# IRcircuit.net
KiCad netlist of a schematic drawn in EAGLE
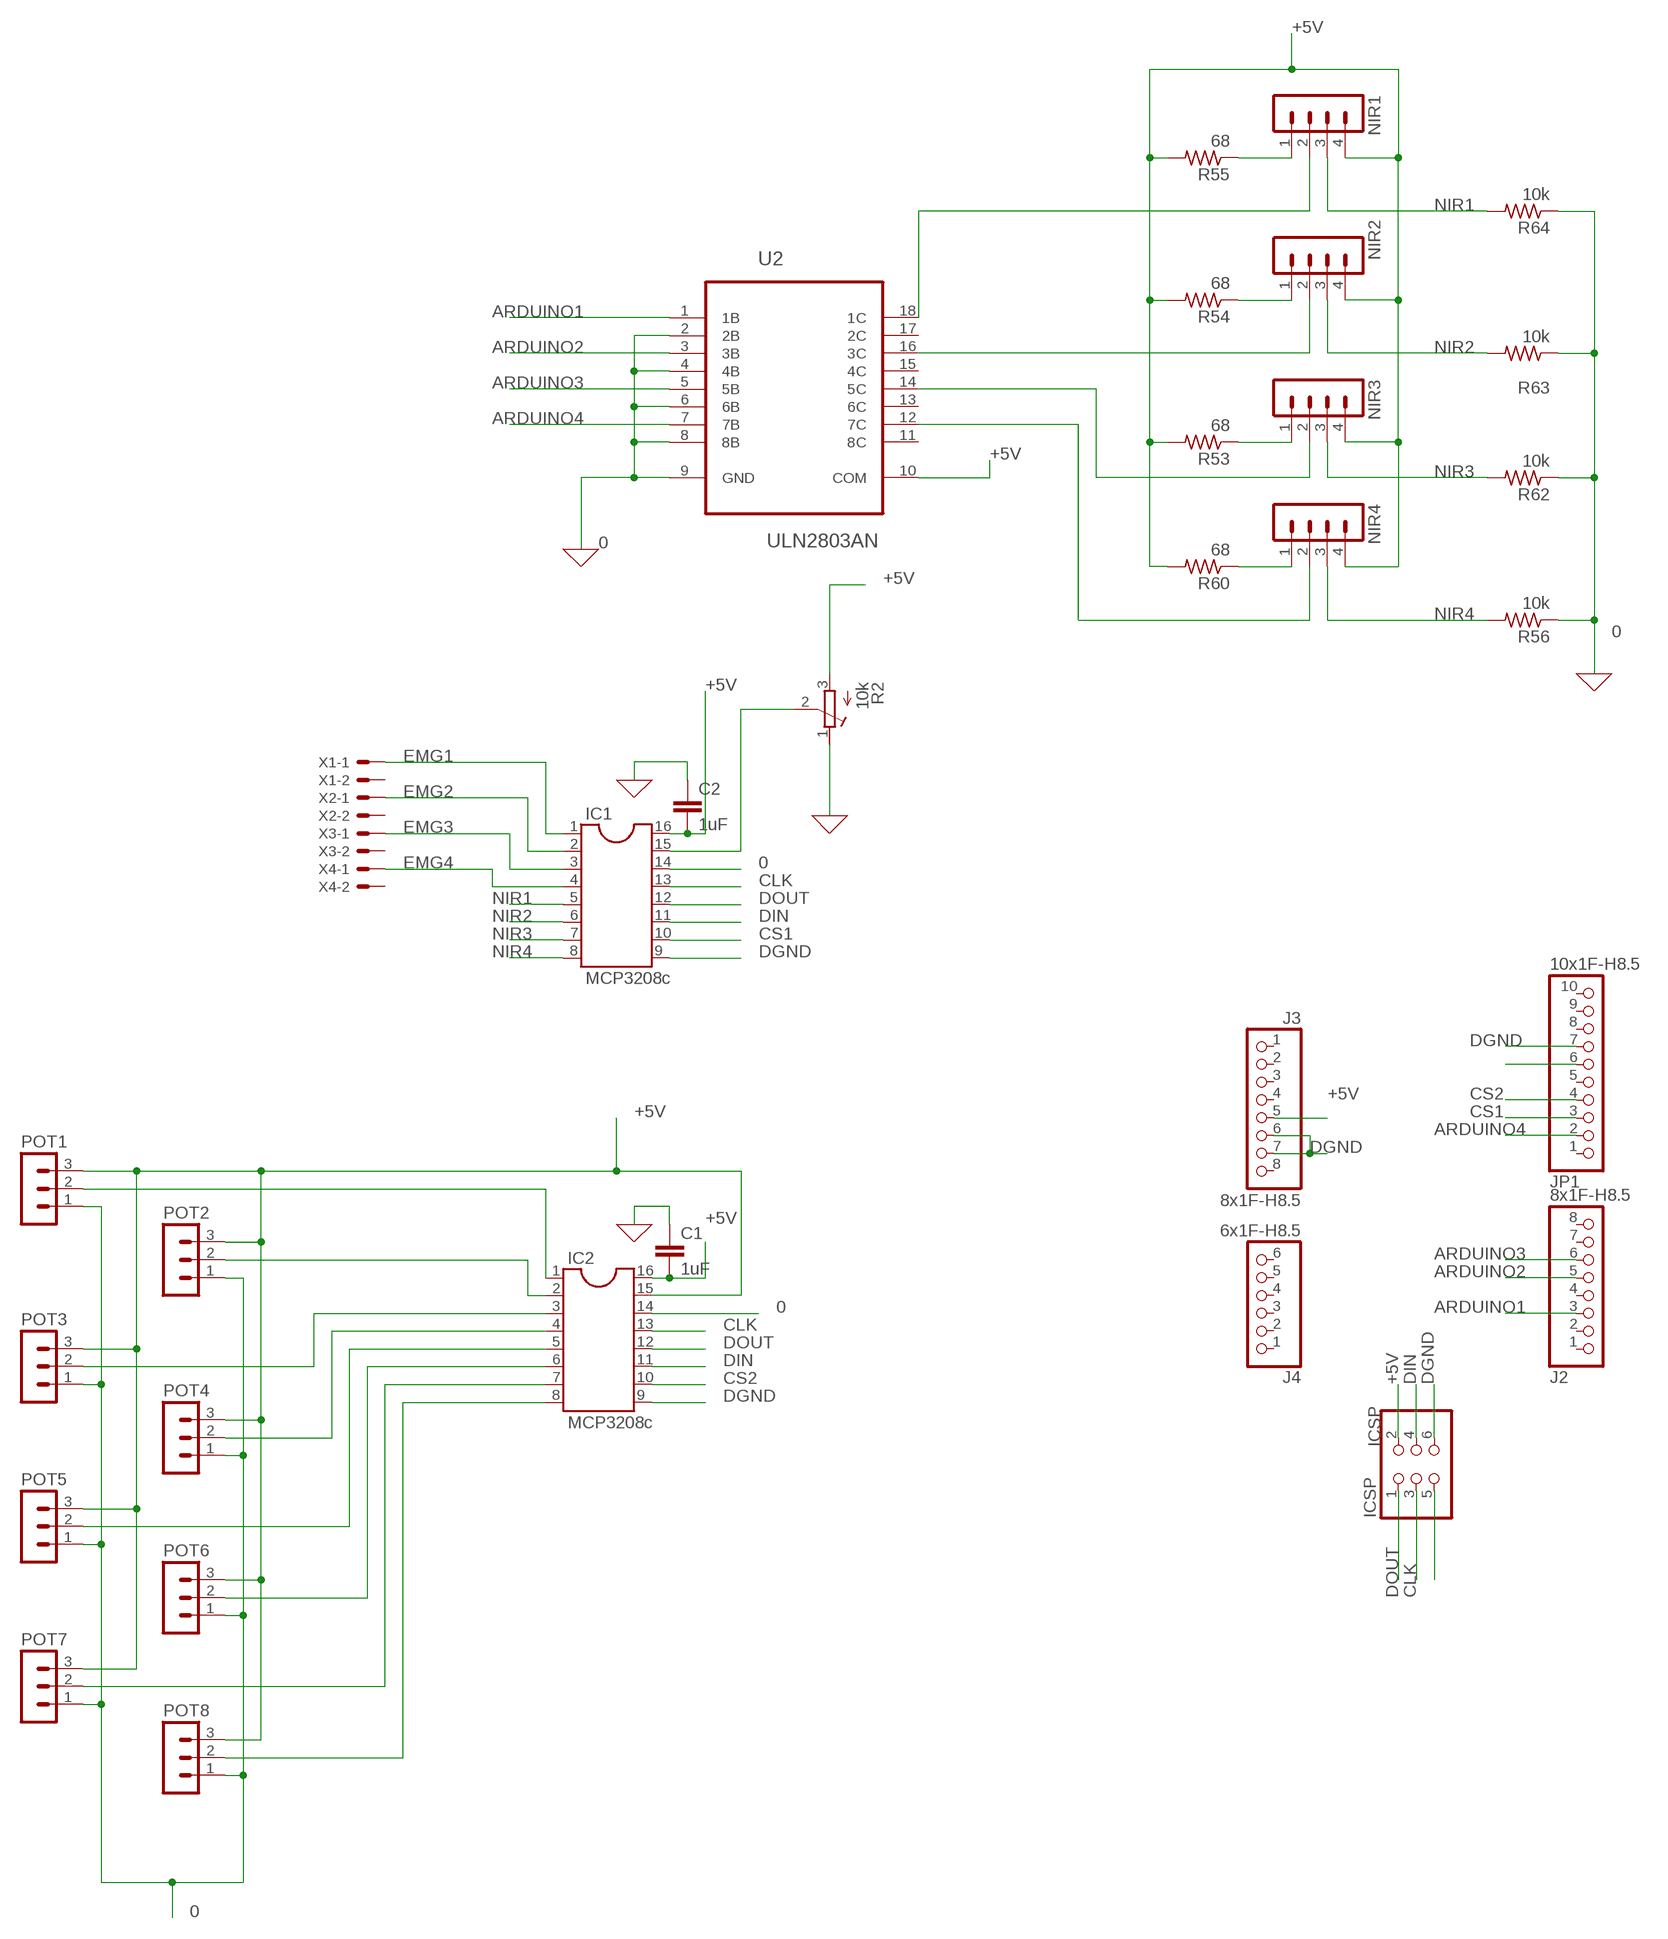
[diagram p0: schematic, sheet 1]

(export (version "E")
  (design (tool "Eeschema 10.0.6"))
  (components
    (comp (ref "C1")
      (value "1uF")
      (footprint "eagle-import:C050-025X075")
      (libsource (lib "eagle-import") (part "C-EU050-025X075"))
    )
    (comp (ref "C2")
      (value "1uF")
      (footprint "eagle-import:C050-025X075")
      (libsource (lib "eagle-import") (part "C-EU050-025X075"))
    )
    (comp (ref "IC1")
      (value "MCP3208c")
      (footprint "eagle-import:DIL16")
      (libsource (lib "eagle-import") (part "DIL16"))
    )
    (comp (ref "IC2")
      (value "MCP3208c")
      (footprint "eagle-import:DIL16")
      (libsource (lib "eagle-import") (part "DIL16"))
    )
    (comp (ref "ICSP")
      (value "ICSP")
      (footprint "eagle-import:2X03")
      (libsource (lib "eagle-import") (part "PINHD-2X3"))
    )
    (comp (ref "J2")
      (value "8x1F-H8.5")
      (footprint "eagle-import:1X08")
      (libsource (lib "eagle-import") (part "PINHD-1X8"))
    )
    (comp (ref "J3")
      (value "8x1F-H8.5")
      (footprint "eagle-import:1X08")
      (libsource (lib "eagle-import") (part "PINHD-1X8"))
    )
    (comp (ref "J4")
      (value "6x1F-H8.5")
      (footprint "eagle-import:1X06")
      (libsource (lib "eagle-import") (part "PINHD-1X6"))
    )
    (comp (ref "JP1")
      (value "10x1F-H8.5")
      (footprint "eagle-import:1X10")
      (libsource (lib "eagle-import") (part "PINHD-1X10"))
    )
    (comp (ref "NIR1")
      (value "MA04-1")
      (footprint "eagle-import:MA04-1")
      (libsource (lib "eagle-import") (part "MA04-1"))
    )
    (comp (ref "NIR2")
      (value "MA04-1")
      (footprint "eagle-import:MA04-1")
      (libsource (lib "eagle-import") (part "MA04-1"))
    )
    (comp (ref "NIR3")
      (value "MA04-1")
      (footprint "eagle-import:MA04-1")
      (libsource (lib "eagle-import") (part "MA04-1"))
    )
    (comp (ref "NIR4")
      (value "MA04-1")
      (footprint "eagle-import:MA04-1")
      (libsource (lib "eagle-import") (part "MA04-1"))
    )
    (comp (ref "POT1")
      (value "MA03-1")
      (footprint "eagle-import:MA03-1")
      (libsource (lib "eagle-import") (part "MA03-1"))
    )
    (comp (ref "POT2")
      (value "MA03-1")
      (footprint "eagle-import:MA03-1")
      (libsource (lib "eagle-import") (part "MA03-1"))
    )
    (comp (ref "POT3")
      (value "MA03-1")
      (footprint "eagle-import:MA03-1")
      (libsource (lib "eagle-import") (part "MA03-1"))
    )
    (comp (ref "POT4")
      (value "MA03-1")
      (footprint "eagle-import:MA03-1")
      (libsource (lib "eagle-import") (part "MA03-1"))
    )
    (comp (ref "POT5")
      (value "MA03-1")
      (footprint "eagle-import:MA03-1")
      (libsource (lib "eagle-import") (part "MA03-1"))
    )
    (comp (ref "POT6")
      (value "MA03-1")
      (footprint "eagle-import:MA03-1")
      (libsource (lib "eagle-import") (part "MA03-1"))
    )
    (comp (ref "POT7")
      (value "MA03-1")
      (footprint "eagle-import:MA03-1")
      (libsource (lib "eagle-import") (part "MA03-1"))
    )
    (comp (ref "POT8")
      (value "MA03-1")
      (footprint "eagle-import:MA03-1")
      (libsource (lib "eagle-import") (part "MA03-1"))
    )
    (comp (ref "R2")
      (value "10k")
      (footprint "eagle-import:RTRIMT93YA")
      (libsource (lib "eagle-import") (part "R-TRIMMT93YA"))
    )
    (comp (ref "R53")
      (value "68")
      (footprint "eagle-import:0207_12")
      (libsource (lib "eagle-import") (part "R-US_0207/12"))
    )
    (comp (ref "R54")
      (value "68")
      (footprint "eagle-import:0207_12")
      (libsource (lib "eagle-import") (part "R-US_0207/12"))
    )
    (comp (ref "R55")
      (value "68")
      (footprint "eagle-import:0207_12")
      (libsource (lib "eagle-import") (part "R-US_0207/12"))
    )
    (comp (ref "R56")
      (value "10k")
      (footprint "eagle-import:0207_12")
      (libsource (lib "eagle-import") (part "R-US_0207/12"))
    )
    (comp (ref "R60")
      (value "68")
      (footprint "eagle-import:0207_12")
      (libsource (lib "eagle-import") (part "R-US_0207/12"))
    )
    (comp (ref "R62")
      (value "10k")
      (footprint "eagle-import:0207_12")
      (libsource (lib "eagle-import") (part "R-US_0207/12"))
    )
    (comp (ref "R63")
      (value "10k")
      (footprint "eagle-import:0207_12")
      (libsource (lib "eagle-import") (part "R-US_0207/12"))
    )
    (comp (ref "R64")
      (value "10k")
      (footprint "eagle-import:0207_12")
      (libsource (lib "eagle-import") (part "R-US_0207/12"))
    )
    (comp (ref "U2")
      (value "ULN2803AN")
      (footprint "eagle-import:DIP254P762X393-18")
      (libsource (lib "eagle-import") (part "ULN2803AN"))
    )
    (comp (ref "X1")
      (value "332-02")
      (footprint "eagle-import:332-02")
      (libsource (lib "eagle-import") (part "332-02"))
    )
    (comp (ref "X2")
      (value "332-02")
      (footprint "eagle-import:332-02")
      (libsource (lib "eagle-import") (part "332-02"))
    )
    (comp (ref "X3")
      (value "332-02")
      (footprint "eagle-import:332-02")
      (libsource (lib "eagle-import") (part "332-02"))
    )
    (comp (ref "X4")
      (value "332-02")
      (footprint "eagle-import:332-02")
      (libsource (lib "eagle-import") (part "332-02"))
    )
  )
  (nets
    (net (code "1") (name "+5V") (class "Default")
      (node (ref "C1") (pin "2") (pinfunction "2_2") (pintype "passive"))
      (node (ref "C2") (pin "2") (pinfunction "2_2") (pintype "passive"))
      (node (ref "IC1") (pin "16") (pinfunction "16_16") (pintype "passive"))
      (node (ref "IC2") (pin "15") (pinfunction "15_15") (pintype "passive"))
      (node (ref "IC2") (pin "16") (pinfunction "16_16") (pintype "passive"))
      (node (ref "ICSP") (pin "2") (pinfunction "2_2") (pintype "passive"))
      (node (ref "J3") (pin "5") (pinfunction "5_5") (pintype "passive"))
      (node (ref "NIR1") (pin "4") (pinfunction "4_4") (pintype "passive"))
      (node (ref "NIR2") (pin "4") (pinfunction "4_4") (pintype "passive"))
      (node (ref "NIR3") (pin "4") (pinfunction "4_4") (pintype "passive"))
      (node (ref "NIR4") (pin "4") (pinfunction "4_4") (pintype "passive"))
      (node (ref "POT1") (pin "3") (pinfunction "3_3") (pintype "passive"))
      (node (ref "POT2") (pin "3") (pinfunction "3_3") (pintype "passive"))
      (node (ref "POT3") (pin "3") (pinfunction "3_3") (pintype "passive"))
      (node (ref "POT4") (pin "3") (pinfunction "3_3") (pintype "passive"))
      (node (ref "POT5") (pin "3") (pinfunction "3_3") (pintype "passive"))
      (node (ref "POT6") (pin "3") (pinfunction "3_3") (pintype "passive"))
      (node (ref "POT7") (pin "3") (pinfunction "3_3") (pintype "passive"))
      (node (ref "POT8") (pin "3") (pinfunction "3_3") (pintype "passive"))
      (node (ref "R2") (pin "3") (pinfunction "A_3") (pintype "passive"))
      (node (ref "R53") (pin "2") (pinfunction "2_2") (pintype "passive"))
      (node (ref "R54") (pin "2") (pinfunction "2_2") (pintype "passive"))
      (node (ref "R55") (pin "2") (pinfunction "2_2") (pintype "passive"))
      (node (ref "R60") (pin "2") (pinfunction "2_2") (pintype "passive"))
      (node (ref "U2") (pin "10") (pinfunction "COM_10") (pintype "output"))
    )
    (net (code "2") (name "0") (class "Default")
      (node (ref "C1") (pin "1") (pinfunction "1_1") (pintype "passive"))
      (node (ref "C2") (pin "1") (pinfunction "1_1") (pintype "passive"))
      (node (ref "IC1") (pin "14") (pinfunction "14_14") (pintype "passive"))
      (node (ref "IC2") (pin "14") (pinfunction "14_14") (pintype "passive"))
      (node (ref "POT1") (pin "1") (pinfunction "1_1") (pintype "passive"))
      (node (ref "POT2") (pin "1") (pinfunction "1_1") (pintype "passive"))
      (node (ref "POT3") (pin "1") (pinfunction "1_1") (pintype "passive"))
      (node (ref "POT4") (pin "1") (pinfunction "1_1") (pintype "passive"))
      (node (ref "POT5") (pin "1") (pinfunction "1_1") (pintype "passive"))
      (node (ref "POT6") (pin "1") (pinfunction "1_1") (pintype "passive"))
      (node (ref "POT7") (pin "1") (pinfunction "1_1") (pintype "passive"))
      (node (ref "POT8") (pin "1") (pinfunction "1_1") (pintype "passive"))
      (node (ref "R2") (pin "1") (pinfunction "E_1") (pintype "passive"))
      (node (ref "R56") (pin "1") (pinfunction "1_1") (pintype "passive"))
      (node (ref "R62") (pin "1") (pinfunction "1_1") (pintype "passive"))
      (node (ref "R63") (pin "1") (pinfunction "1_1") (pintype "passive"))
      (node (ref "R64") (pin "1") (pinfunction "1_1") (pintype "passive"))
      (node (ref "U2") (pin "2") (pinfunction "2B_2") (pintype "input"))
      (node (ref "U2") (pin "4") (pinfunction "4B_4") (pintype "input"))
      (node (ref "U2") (pin "6") (pinfunction "6B_6") (pintype "input"))
      (node (ref "U2") (pin "8") (pinfunction "8B_8") (pintype "input"))
      (node (ref "U2") (pin "9") (pinfunction "GND_9") (pintype "passive"))
    )
    (net (code "3") (name "ARDUINO1") (class "Default")
      (node (ref "J2") (pin "3") (pinfunction "3_3") (pintype "passive"))
      (node (ref "U2") (pin "1") (pinfunction "1B_1") (pintype "input"))
    )
    (net (code "4") (name "ARDUINO2") (class "Default")
      (node (ref "J2") (pin "5") (pinfunction "5_5") (pintype "passive"))
      (node (ref "U2") (pin "3") (pinfunction "3B_3") (pintype "input"))
    )
    (net (code "5") (name "ARDUINO3") (class "Default")
      (node (ref "J2") (pin "6") (pinfunction "6_6") (pintype "passive"))
      (node (ref "U2") (pin "5") (pinfunction "5B_5") (pintype "input"))
    )
    (net (code "6") (name "ARDUINO4") (class "Default")
      (node (ref "JP1") (pin "2") (pinfunction "2_2") (pintype "passive"))
      (node (ref "U2") (pin "7") (pinfunction "7B_7") (pintype "input"))
    )
    (net (code "7") (name "CLK") (class "Default")
      (node (ref "IC1") (pin "13") (pinfunction "13_13") (pintype "passive"))
      (node (ref "IC2") (pin "13") (pinfunction "13_13") (pintype "passive"))
      (node (ref "ICSP") (pin "3") (pinfunction "3_3") (pintype "passive"))
    )
    (net (code "8") (name "CS1") (class "Default")
      (node (ref "IC1") (pin "10") (pinfunction "10_10") (pintype "passive"))
      (node (ref "JP1") (pin "3") (pinfunction "3_3") (pintype "passive"))
    )
    (net (code "9") (name "CS2") (class "Default")
      (node (ref "IC2") (pin "10") (pinfunction "10_10") (pintype "passive"))
      (node (ref "JP1") (pin "4") (pinfunction "4_4") (pintype "passive"))
    )
    (net (code "10") (name "DGND") (class "Default")
      (node (ref "IC1") (pin "9") (pinfunction "9_9") (pintype "passive"))
      (node (ref "IC2") (pin "9") (pinfunction "9_9") (pintype "passive"))
      (node (ref "ICSP") (pin "6") (pinfunction "6_6") (pintype "passive"))
      (node (ref "J3") (pin "6") (pinfunction "6_6") (pintype "passive"))
      (node (ref "J3") (pin "7") (pinfunction "7_7") (pintype "passive"))
      (node (ref "JP1") (pin "7") (pinfunction "7_7") (pintype "passive"))
    )
    (net (code "11") (name "DIN") (class "Default")
      (node (ref "IC1") (pin "11") (pinfunction "11_11") (pintype "passive"))
      (node (ref "IC2") (pin "11") (pinfunction "11_11") (pintype "passive"))
      (node (ref "ICSP") (pin "4") (pinfunction "4_4") (pintype "passive"))
    )
    (net (code "12") (name "DOUT") (class "Default")
      (node (ref "IC1") (pin "12") (pinfunction "12_12") (pintype "passive"))
      (node (ref "IC2") (pin "12") (pinfunction "12_12") (pintype "passive"))
      (node (ref "ICSP") (pin "1") (pinfunction "1_1") (pintype "passive"))
    )
    (net (code "13") (name "EMG1") (class "Default")
      (node (ref "IC1") (pin "1") (pinfunction "1_1") (pintype "passive"))
      (node (ref "X1") (pin "1") (pinfunction "S_1") (pintype "passive"))
    )
    (net (code "14") (name "EMG2") (class "Default")
      (node (ref "IC1") (pin "2") (pinfunction "2_2") (pintype "passive"))
      (node (ref "X2") (pin "1") (pinfunction "S_1") (pintype "passive"))
    )
    (net (code "15") (name "EMG3") (class "Default")
      (node (ref "IC1") (pin "3") (pinfunction "3_3") (pintype "passive"))
      (node (ref "X3") (pin "1") (pinfunction "S_1") (pintype "passive"))
    )
    (net (code "16") (name "EMG4") (class "Default")
      (node (ref "IC1") (pin "4") (pinfunction "4_4") (pintype "passive"))
      (node (ref "X4") (pin "1") (pinfunction "S_1") (pintype "passive"))
    )
    (net (code "17") (name "NIR1") (class "Default")
      (node (ref "IC1") (pin "5") (pinfunction "5_5") (pintype "passive"))
      (node (ref "NIR1") (pin "3") (pinfunction "3_3") (pintype "passive"))
      (node (ref "R64") (pin "2") (pinfunction "2_2") (pintype "passive"))
    )
    (net (code "18") (name "NIR2") (class "Default")
      (node (ref "IC1") (pin "6") (pinfunction "6_6") (pintype "passive"))
      (node (ref "NIR2") (pin "3") (pinfunction "3_3") (pintype "passive"))
      (node (ref "R63") (pin "2") (pinfunction "2_2") (pintype "passive"))
    )
    (net (code "19") (name "NIR3") (class "Default")
      (node (ref "IC1") (pin "7") (pinfunction "7_7") (pintype "passive"))
      (node (ref "NIR3") (pin "3") (pinfunction "3_3") (pintype "passive"))
      (node (ref "R62") (pin "2") (pinfunction "2_2") (pintype "passive"))
    )
    (net (code "20") (name "NIR4") (class "Default")
      (node (ref "IC1") (pin "8") (pinfunction "8_8") (pintype "passive"))
      (node (ref "NIR4") (pin "3") (pinfunction "3_3") (pintype "passive"))
      (node (ref "R56") (pin "2") (pinfunction "2_2") (pintype "passive"))
    )
    (net (code "21") (name "Net-(IC2-Pad1)") (class "Default")
      (node (ref "IC2") (pin "1") (pinfunction "1_1") (pintype "passive"))
      (node (ref "POT1") (pin "2") (pinfunction "2_2") (pintype "passive"))
    )
    (net (code "22") (name "Net-(IC2-Pad2)") (class "Default")
      (node (ref "IC2") (pin "2") (pinfunction "2_2") (pintype "passive"))
      (node (ref "POT2") (pin "2") (pinfunction "2_2") (pintype "passive"))
    )
    (net (code "23") (name "Net-(IC2-Pad3)") (class "Default")
      (node (ref "IC2") (pin "3") (pinfunction "3_3") (pintype "passive"))
      (node (ref "POT3") (pin "2") (pinfunction "2_2") (pintype "passive"))
    )
    (net (code "24") (name "Net-(IC2-Pad4)") (class "Default")
      (node (ref "IC2") (pin "4") (pinfunction "4_4") (pintype "passive"))
      (node (ref "POT4") (pin "2") (pinfunction "2_2") (pintype "passive"))
    )
    (net (code "25") (name "Net-(IC2-Pad5)") (class "Default")
      (node (ref "IC2") (pin "5") (pinfunction "5_5") (pintype "passive"))
      (node (ref "POT5") (pin "2") (pinfunction "2_2") (pintype "passive"))
    )
    (net (code "26") (name "Net-(IC2-Pad6)") (class "Default")
      (node (ref "IC2") (pin "6") (pinfunction "6_6") (pintype "passive"))
      (node (ref "POT6") (pin "2") (pinfunction "2_2") (pintype "passive"))
    )
    (net (code "27") (name "Net-(IC2-Pad7)") (class "Default")
      (node (ref "IC2") (pin "7") (pinfunction "7_7") (pintype "passive"))
      (node (ref "POT7") (pin "2") (pinfunction "2_2") (pintype "passive"))
    )
    (net (code "28") (name "Net-(IC2-Pad8)") (class "Default")
      (node (ref "IC2") (pin "8") (pinfunction "8_8") (pintype "passive"))
      (node (ref "POT8") (pin "2") (pinfunction "2_2") (pintype "passive"))
    )
    (net (code "29") (name "Net-(NIR1-Pad1)") (class "Default")
      (node (ref "NIR1") (pin "1") (pinfunction "1_1") (pintype "passive"))
      (node (ref "R55") (pin "1") (pinfunction "1_1") (pintype "passive"))
    )
    (net (code "30") (name "Net-(NIR2-Pad1)") (class "Default")
      (node (ref "NIR2") (pin "1") (pinfunction "1_1") (pintype "passive"))
      (node (ref "R54") (pin "1") (pinfunction "1_1") (pintype "passive"))
    )
    (net (code "31") (name "Net-(NIR3-Pad1)") (class "Default")
      (node (ref "NIR3") (pin "1") (pinfunction "1_1") (pintype "passive"))
      (node (ref "R53") (pin "1") (pinfunction "1_1") (pintype "passive"))
    )
    (net (code "32") (name "Net-(NIR4-Pad1)") (class "Default")
      (node (ref "NIR4") (pin "1") (pinfunction "1_1") (pintype "passive"))
      (node (ref "R60") (pin "1") (pinfunction "1_1") (pintype "passive"))
    )
    (net (code "33") (name "Net-(R2-S)") (class "Default")
      (node (ref "IC1") (pin "15") (pinfunction "15_15") (pintype "passive"))
      (node (ref "R2") (pin "2") (pinfunction "S_2") (pintype "passive"))
    )
    (net (code "34") (name "Net-(U2-1C)") (class "Default")
      (node (ref "NIR1") (pin "2") (pinfunction "2_2") (pintype "passive"))
      (node (ref "U2") (pin "18") (pinfunction "1C_18") (pintype "output"))
    )
    (net (code "35") (name "Net-(U2-3C)") (class "Default")
      (node (ref "NIR2") (pin "2") (pinfunction "2_2") (pintype "passive"))
      (node (ref "U2") (pin "16") (pinfunction "3C_16") (pintype "output"))
    )
    (net (code "36") (name "Net-(U2-5C)") (class "Default")
      (node (ref "NIR3") (pin "2") (pinfunction "2_2") (pintype "passive"))
      (node (ref "U2") (pin "14") (pinfunction "5C_14") (pintype "output"))
    )
    (net (code "37") (name "Net-(U2-7C)") (class "Default")
      (node (ref "NIR4") (pin "2") (pinfunction "2_2") (pintype "passive"))
      (node (ref "U2") (pin "12") (pinfunction "7C_12") (pintype "output"))
    )
    (net (code "38") (name "unconnected-(ICSP-Pad5)") (class "Default")
      (node (ref "ICSP") (pin "5") (pinfunction "5_5") (pintype "passive"))
    )
    (net (code "39") (name "unconnected-(J2-Pad1)") (class "Default")
      (node (ref "J2") (pin "1") (pinfunction "1_1") (pintype "passive"))
    )
    (net (code "40") (name "unconnected-(J2-Pad2)") (class "Default")
      (node (ref "J2") (pin "2") (pinfunction "2_2") (pintype "passive"))
    )
    (net (code "41") (name "unconnected-(J2-Pad4)") (class "Default")
      (node (ref "J2") (pin "4") (pinfunction "4_4") (pintype "passive"))
    )
    (net (code "42") (name "unconnected-(J2-Pad7)") (class "Default")
      (node (ref "J2") (pin "7") (pinfunction "7_7") (pintype "passive"))
    )
    (net (code "43") (name "unconnected-(J2-Pad8)") (class "Default")
      (node (ref "J2") (pin "8") (pinfunction "8_8") (pintype "passive"))
    )
    (net (code "44") (name "unconnected-(J3-Pad1)") (class "Default")
      (node (ref "J3") (pin "1") (pinfunction "1_1") (pintype "passive"))
    )
    (net (code "45") (name "unconnected-(J3-Pad2)") (class "Default")
      (node (ref "J3") (pin "2") (pinfunction "2_2") (pintype "passive"))
    )
    (net (code "46") (name "unconnected-(J3-Pad3)") (class "Default")
      (node (ref "J3") (pin "3") (pinfunction "3_3") (pintype "passive"))
    )
    (net (code "47") (name "unconnected-(J3-Pad4)") (class "Default")
      (node (ref "J3") (pin "4") (pinfunction "4_4") (pintype "passive"))
    )
    (net (code "48") (name "unconnected-(J3-Pad8)") (class "Default")
      (node (ref "J3") (pin "8") (pinfunction "8_8") (pintype "passive"))
    )
    (net (code "49") (name "unconnected-(J4-Pad1)") (class "Default")
      (node (ref "J4") (pin "1") (pinfunction "1_1") (pintype "passive"))
    )
    (net (code "50") (name "unconnected-(J4-Pad2)") (class "Default")
      (node (ref "J4") (pin "2") (pinfunction "2_2") (pintype "passive"))
    )
    (net (code "51") (name "unconnected-(J4-Pad3)") (class "Default")
      (node (ref "J4") (pin "3") (pinfunction "3_3") (pintype "passive"))
    )
    (net (code "52") (name "unconnected-(J4-Pad4)") (class "Default")
      (node (ref "J4") (pin "4") (pinfunction "4_4") (pintype "passive"))
    )
    (net (code "53") (name "unconnected-(J4-Pad5)") (class "Default")
      (node (ref "J4") (pin "5") (pinfunction "5_5") (pintype "passive"))
    )
    (net (code "54") (name "unconnected-(J4-Pad6)") (class "Default")
      (node (ref "J4") (pin "6") (pinfunction "6_6") (pintype "passive"))
    )
    (net (code "55") (name "unconnected-(JP1-Pad1)") (class "Default")
      (node (ref "JP1") (pin "1") (pinfunction "1_1") (pintype "passive"))
    )
    (net (code "56") (name "unconnected-(JP1-Pad5)") (class "Default")
      (node (ref "JP1") (pin "5") (pinfunction "5_5") (pintype "passive"))
    )
    (net (code "57") (name "unconnected-(JP1-Pad6)") (class "Default")
      (node (ref "JP1") (pin "6") (pinfunction "6_6") (pintype "passive"))
    )
    (net (code "58") (name "unconnected-(JP1-Pad8)") (class "Default")
      (node (ref "JP1") (pin "8") (pinfunction "8_8") (pintype "passive"))
    )
    (net (code "59") (name "unconnected-(JP1-Pad9)") (class "Default")
      (node (ref "JP1") (pin "9") (pinfunction "9_9") (pintype "passive"))
    )
    (net (code "60") (name "unconnected-(JP1-Pad10)") (class "Default")
      (node (ref "JP1") (pin "10") (pinfunction "10_10") (pintype "passive"))
    )
    (net (code "61") (name "unconnected-(U2-2C-Pad17)") (class "Default")
      (node (ref "U2") (pin "17") (pinfunction "2C_17") (pintype "output"))
    )
    (net (code "62") (name "unconnected-(U2-4C-Pad15)") (class "Default")
      (node (ref "U2") (pin "15") (pinfunction "4C_15") (pintype "output"))
    )
    (net (code "63") (name "unconnected-(U2-6C-Pad13)") (class "Default")
      (node (ref "U2") (pin "13") (pinfunction "6C_13") (pintype "output"))
    )
    (net (code "64") (name "unconnected-(U2-8C-Pad11)") (class "Default")
      (node (ref "U2") (pin "11") (pinfunction "8C_11") (pintype "output"))
    )
    (net (code "65") (name "unconnected-(X1B-S-Pad2)") (class "Default")
      (node (ref "X1") (pin "2") (pinfunction "S_2") (pintype "passive"))
    )
    (net (code "66") (name "unconnected-(X2B-S-Pad2)") (class "Default")
      (node (ref "X2") (pin "2") (pinfunction "S_2") (pintype "passive"))
    )
    (net (code "67") (name "unconnected-(X3B-S-Pad2)") (class "Default")
      (node (ref "X3") (pin "2") (pinfunction "S_2") (pintype "passive"))
    )
    (net (code "68") (name "unconnected-(X4B-S-Pad2)") (class "Default")
      (node (ref "X4") (pin "2") (pinfunction "S_2") (pintype "passive"))
    )
  )
)
